# wisp-6-afe.net
KiCad netlist of a schematic drawn in Altium Designer
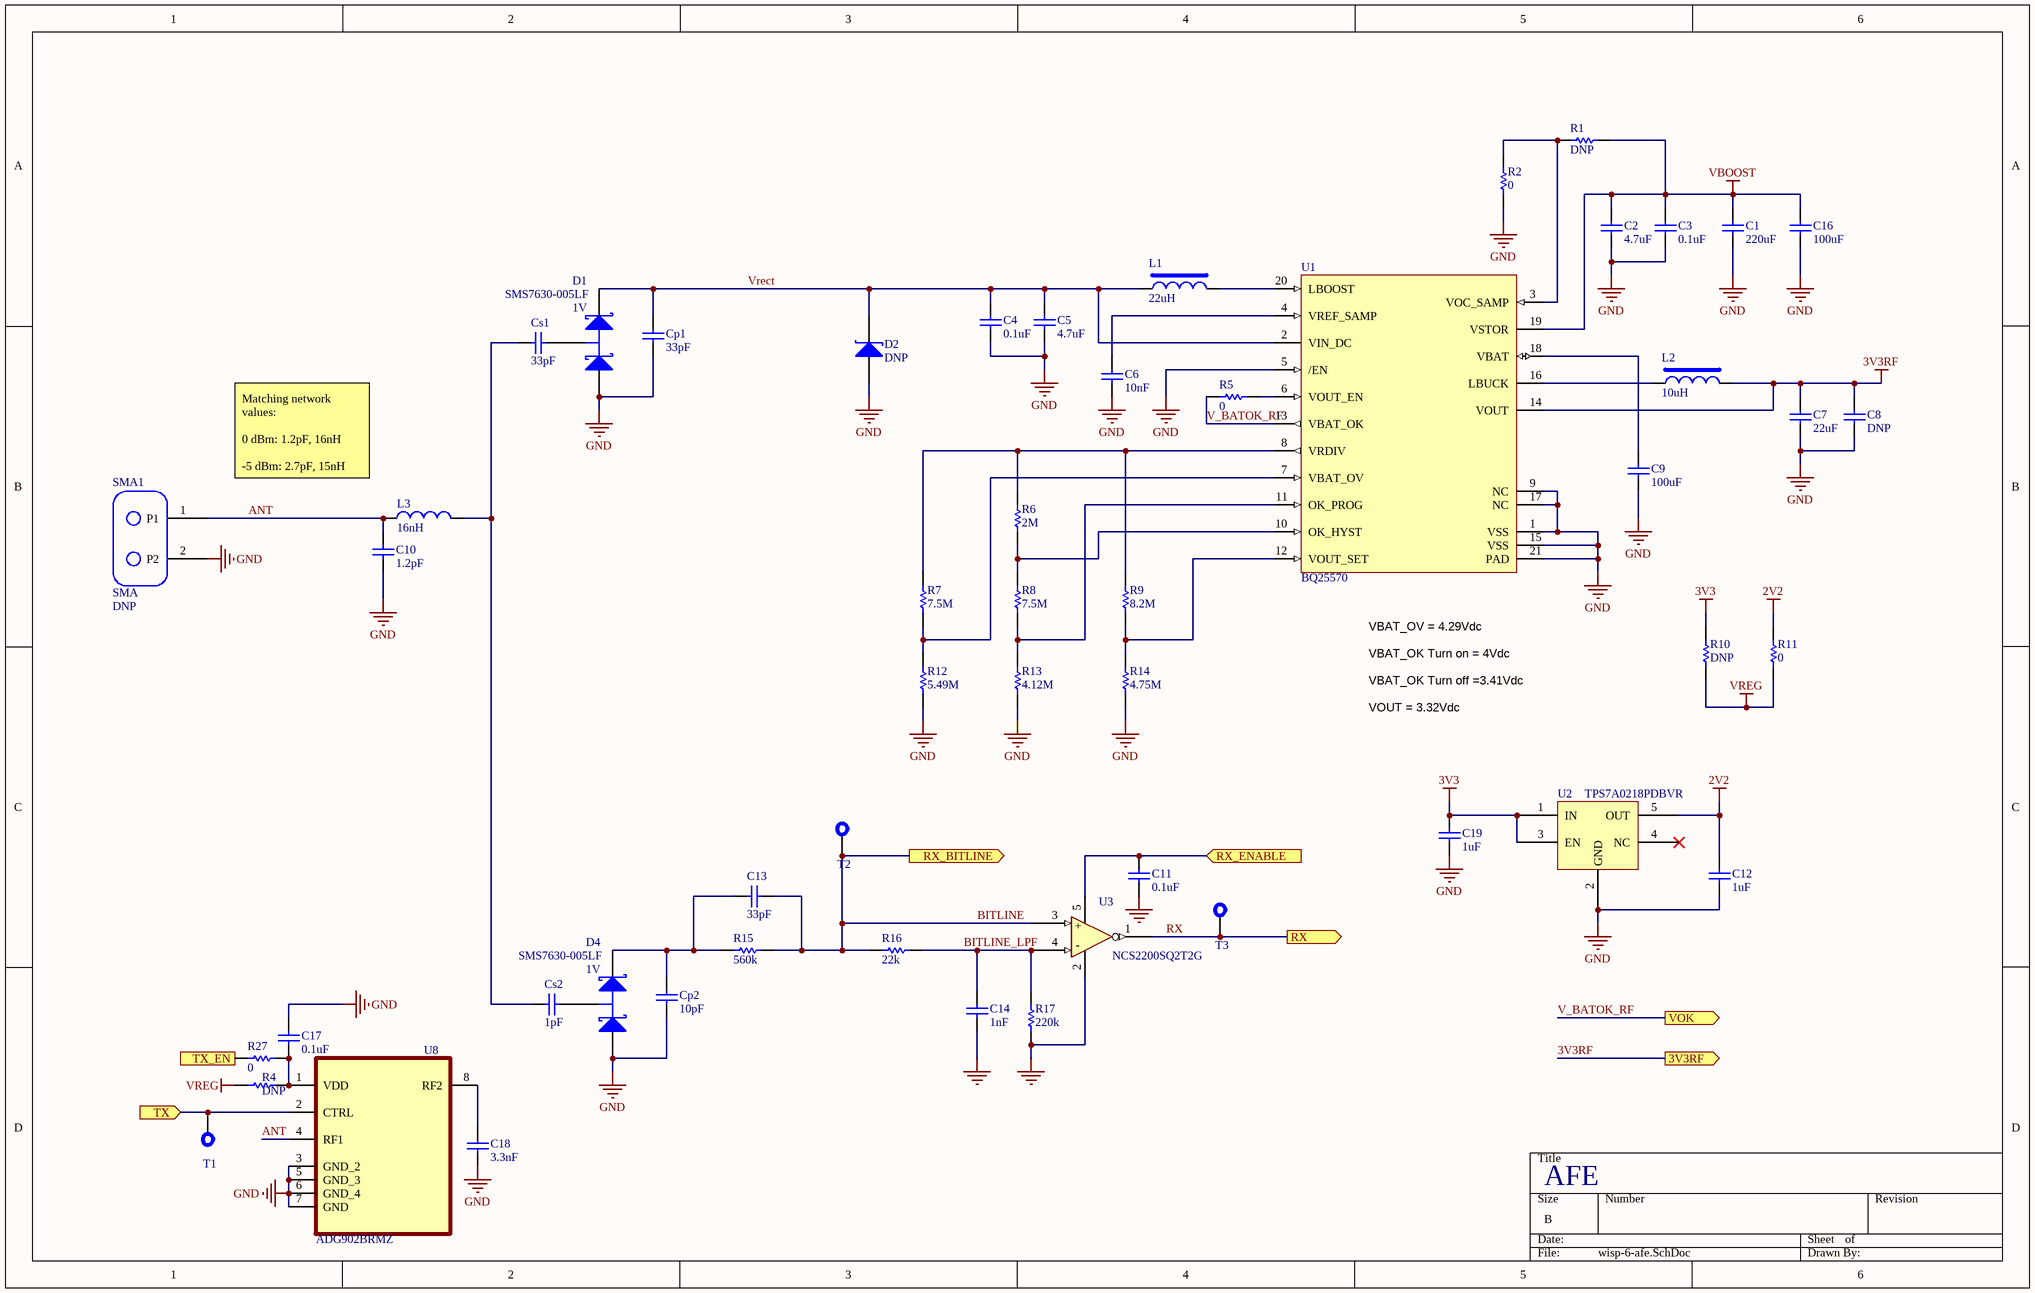
[diagram p0: wisp-6-afe.SchDoc]

(export (version "E")
  (design (tool "Eeschema 10.0.6"))
  (components
    (comp (ref "C1")
      (value "220uF")
      (footprint "1206")
      (description "CAP CER 220UF 6.3V X5R 1206")
      (fields
        (field (name "DIGI-KEY PART NUMBER") "490-13970-1-ND")
        (field (name "MANUFACTURER") "Murata Electronics")
      )
      (libsource (lib "WISP6") (part "C-220uF-6V3-X5R-1206"))
    )
    (comp (ref "C2")
      (value "4.7uF")
      (footprint "0402")
      (description "CAP CER 4.7UF 10V X5R 0402")
      (fields
        (field (name "DIGI-KEY PART NUMBER") "1276-1482-1-ND")
        (field (name "MANUFACTURER") "Samsung Electro-Mechanics")
      )
      (libsource (lib "WISP6") (part "C-4.7uF-10V-X5R-0402"))
    )
    (comp (ref "C3")
      (value "0.1uF")
      (footprint "0402")
      (description "CAP CER 100nF/0.1UF 10V X5R 0402")
      (fields
        (field (name "DIGI-KEY PART NUMBER") "1276-1022-1-ND")
        (field (name "MANUFACTURER") "Samsung Electro-Mechanics")
      )
      (libsource (lib "WISP6") (part "C-0.1uF-10V-X5R-0402"))
    )
    (comp (ref "C4")
      (value "0.1uF")
      (footprint "0402")
      (description "CAP CER 100nF/0.1UF 10V X5R 0402")
      (fields
        (field (name "DIGI-KEY PART NUMBER") "1276-1022-1-ND")
        (field (name "MANUFACTURER") "Samsung Electro-Mechanics")
      )
      (libsource (lib "WISP6") (part "C-0.1uF-10V-X5R-0402"))
    )
    (comp (ref "C5")
      (value "4.7uF")
      (footprint "0402")
      (description "CAP CER 4.7UF 10V X5R 0402")
      (fields
        (field (name "DIGI-KEY PART NUMBER") "1276-1482-1-ND")
        (field (name "MANUFACTURER") "Samsung Electro-Mechanics")
      )
      (libsource (lib "WISP6") (part "C-4.7uF-10V-X5R-0402"))
    )
    (comp (ref "C6")
      (value "10nF")
      (footprint "0402")
      (description "10000 pF ±10% 50V Ceramic Capacitor X7R 0402 (1005 Metric)")
      (fields
        (field (name "DIGI-KEY PART NUMBER") "1276-1028-1-ND")
        (field (name "MANUFACTURER") "Samsung Electro-Mechanics")
      )
      (libsource (lib "WISP6") (part "C-10nF-50V-X7R-0402"))
    )
    (comp (ref "C7")
      (value "22uF")
      (footprint "0402")
      (description "CAP CER 22UF 6.3V X5R 0402")
      (fields
        (field (name "DIGI-KEY PART NUMBER") "1276-7090-1-ND")
        (field (name "MANUFACTURER") "Samsung Electro-Mechanics")
      )
      (libsource (lib "WISP6") (part "C-22uF-6V3-X5R-0402"))
    )
    (comp (ref "C8")
      (value "DNP")
      (footprint "0402")
      (description "Ceramic Capacitor (Surface Mount)")
      (fields (field (name "Comment") "Generic capacitor"))
      (libsource (lib "WISP6") (part "cap"))
    )
    (comp (ref "C9")
      (value "100uF")
      (footprint "0805")
      (description "CAP CER 100UF 6.3V X5R 0805")
      (fields
        (field (name "DIGI-KEY PART NUMBER") "490-13981-1-ND")
        (field (name "MANUFACTURER") "Murata Electronics")
      )
      (libsource (lib "WISP6") (part "C-100uF-6V3-X5R-0805"))
    )
    (comp (ref "C10")
      (value "1.2pF")
      (footprint "0402")
      (description "Ceramic Capacitor (Surface Mount)")
      (fields
        (field (name "DIGI-KEY PART NUMBER") "712-QSCF500Q1R2A1GV001TCT-ND")
        (field (name "MANUFACTURER") "Johanson Technology Inc.")
      )
      (libsource (lib "WISP6") (part "cap"))
    )
    (comp (ref "C11")
      (value "0.1uF")
      (footprint "0402")
      (description "CAP CER 100nF/0.1UF 10V X5R 0402")
      (fields
        (field (name "DIGI-KEY PART NUMBER") "1276-1022-1-ND")
        (field (name "MANUFACTURER") "Samsung Electro-Mechanics")
      )
      (libsource (lib "WISP6") (part "C-0.1uF-10V-X5R-0402"))
    )
    (comp (ref "C12")
      (value "1uF")
      (footprint "0402")
      (description "CAP CER 1UF 10V X5R 0402")
      (fields
        (field (name "DIGI-KEY PART NUMBER") "1276-1076-1-ND")
        (field (name "MANUFACTURER") "Samsung Electro-Mechanics")
      )
      (libsource (lib "WISP6") (part "C-1uF-10V-X5R-0402"))
    )
    (comp (ref "C13")
      (value "33pF")
      (footprint "0402")
      (description "Ceramic Capacitor (Surface Mount)")
      (fields
        (field (name "DIGI-KEY PART NUMBER") "712-QSCF500Q330F1GV001TCT-ND")
        (field (name "MANUFACTURER") "Johanson Technology Inc.")
      )
      (libsource (lib "WISP6") (part "cap"))
    )
    (comp (ref "C14")
      (value "1nF")
      (footprint "0402")
      (description "CAP CER 1000PF 50V C0G/NP0 0402")
      (fields
        (field (name "DIGI-KEY PART NUMBER") "1276-1635-1-ND")
        (field (name "MANUFACTURER") "Samsung Electro-Mechanics")
      )
      (libsource (lib "WISP6") (part "C-1nF-50V-C0G-0402"))
    )
    (comp (ref "C16")
      (value "100uF")
      (footprint "0805")
      (description "CAP CER 100UF 6.3V X5R 0805")
      (fields
        (field (name "DIGI-KEY PART NUMBER") "490-13981-1-ND")
        (field (name "MANUFACTURER") "Murata Electronics")
      )
      (libsource (lib "WISP6") (part "C-100uF-6V3-X5R-0805"))
    )
    (comp (ref "C17")
      (value "0.1uF")
      (footprint "0402")
      (description "CAP CER 100nF/0.1UF 10V X5R 0402")
      (fields
        (field (name "DIGI-KEY PART NUMBER") "1276-1022-1-ND")
        (field (name "MANUFACTURER") "Samsung Electro-Mechanics")
      )
      (libsource (lib "WISP6") (part "C-0.1uF-10V-X5R-0402"))
    )
    (comp (ref "C18")
      (value "3.3nF")
      (footprint "0402")
      (description "Ceramic Capacitor (Surface Mount)")
      (fields
        (field (name "DIGI-KEY PART NUMBER") "490-GRM1555C1H332GE01DCT-ND")
        (field (name "MANUFACTURER") "Murata Electronics")
      )
      (libsource (lib "WISP6") (part "cap"))
    )
    (comp (ref "C19")
      (value "1uF")
      (footprint "0402")
      (description "CAP CER 1UF 10V X5R 0402")
      (fields
        (field (name "DIGI-KEY PART NUMBER") "1276-1076-1-ND")
        (field (name "MANUFACTURER") "Samsung Electro-Mechanics")
      )
      (libsource (lib "WISP6") (part "C-1uF-10V-X5R-0402"))
    )
    (comp (ref "Cp1")
      (value "33pF")
      (footprint "0402")
      (description "Ceramic Capacitor (Surface Mount)")
      (fields
        (field (name "DIGI-KEY PART NUMBER") "712-QSCF500Q330F1GV001TCT-ND")
        (field (name "MANUFACTURER") "Johanson Technology Inc.")
      )
      (libsource (lib "WISP6") (part "cap"))
    )
    (comp (ref "Cp2")
      (value "10pF")
      (footprint "0402")
      (description "Ceramic Capacitor (Surface Mount)")
      (fields
        (field (name "DIGI-KEY PART NUMBER") "712-QSCF500Q100F1GV001TCT-ND")
        (field (name "MANUFACTURER") "Johanson Technology Inc.")
      )
      (libsource (lib "WISP6") (part "cap"))
    )
    (comp (ref "Cs1")
      (value "33pF")
      (footprint "0402")
      (description "Ceramic Capacitor (Surface Mount)")
      (fields
        (field (name "DIGI-KEY PART NUMBER") "712-QSCF500Q330F1GV001TCT-ND")
        (field (name "MANUFACTURER") "Johanson Technology Inc.")
      )
      (libsource (lib "WISP6") (part "cap"))
    )
    (comp (ref "Cs2")
      (value "1pF")
      (footprint "0402")
      (description "Ceramic Capacitor (Surface Mount)")
      (fields
        (field (name "DIGI-KEY PART NUMBER") "712-QSCF500Q1R0B1GV001TCT-ND")
        (field (name "MANUFACTURER") "Johanson Technology Inc.")
      )
      (libsource (lib "WISP6") (part "cap"))
    )
    (comp (ref "D1")
      (value "SMS7630-005LF")
      (footprint "WISP_AD10:SOT23 - N")
      (description "RF diode schottky\r\nSOT-23 Series Pair\r\nLs=1.5nH")
      (fields
        (field (name "MANUFACTURER") "Skyworks Solutions Inc.")
        (field (name "DIGI-KEY PART NUMBER") "863-1699-1-ND")
        (field (name "ALTIUM_VALUE") "1V")
      )
      (libsource (lib "WISP6") (part "SMS7630-005LF"))
    )
    (comp (ref "D2")
      (value "DNP")
      (footprint "Zener_SOD-523")
      (description "Diode - Zener")
      (fields (field (name "Comment") "Generic diode - zener"))
      (libsource (lib "WISP6") (part "diode_zener"))
    )
    (comp (ref "D4")
      (value "SMS7630-005LF")
      (footprint "WISP_AD10:SOT23 - N")
      (description "RF diode schottky\r\nSOT-23 Series Pair\r\nLs=1.5nH")
      (fields
        (field (name "MANUFACTURER") "Skyworks Solutions Inc.")
        (field (name "DIGI-KEY PART NUMBER") "863-1699-1-ND")
        (field (name "ALTIUM_VALUE") "1V")
      )
      (libsource (lib "WISP6") (part "SMS7630-005LF"))
    )
    (comp (ref "L1")
      (value "22uH")
      (footprint "LPS4018")
      (description "22 µH Shielded Drum Core Inductor 650 mA 360mOhm Max Nonstandard")
      (fields
        (field (name "DIGI-KEY PART NUMBER") "2457-LPS4018-223MRC-ND")
        (field (name "MANUFACTURER") "Coilcraft")
      )
      (libsource (lib "WISP6") (part "Ind-22uH-650mA-20%-LPS4018"))
    )
    (comp (ref "L2")
      (value "10uH")
      (footprint "IND1008")
      (description "FIXED IND 10UH 800MA 625 MOHM")
      (fields
        (field (name "DIGI-KEY PART NUMBER") "732-74479889310CT-ND")
        (field (name "MANUFACTURER") "Würth Elektronik")
      )
      (libsource (lib "WISP6") (part "Ind-10uH-800mA-20%-1008"))
    )
    (comp (ref "L3")
      (value "16nH")
      (footprint "0603")
      (description "Inductor (Surface Mount)")
      (fields
        (field (name "DIGI-KEY PART NUMBER") "490-LQW18AS16NG00DCT-ND")
        (field (name "MANUFACTURER") "Murata Electronics")
      )
      (libsource (lib "WISP6") (part "ind"))
    )
    (comp (ref "R1")
      (value "DNP")
      (footprint "0402")
      (description "Chip Resistor (Surface Mount)")
      (fields (field (name "Comment") "Generic resistor"))
      (libsource (lib "WISP6") (part "res"))
    )
    (comp (ref "R2")
      (value "0")
      (footprint "0402")
      (description "RES 0 OHM JUMPER 1/16W 0402")
      (fields
        (field (name "MANUFACTURER") "YAGEO")
        (field (name "MANUFACTURER PART NUMBER") "RC0402JR-070RL")
      )
      (libsource (lib "WISP6") (part "R-0-0.063W-*-0402"))
    )
    (comp (ref "R4")
      (value "DNP")
      (footprint "0402")
      (description "Chip Resistor (Surface Mount)")
      (fields (field (name "Comment") "Generic resistor"))
      (libsource (lib "WISP6") (part "res"))
    )
    (comp (ref "R5")
      (value "0")
      (footprint "0402")
      (description "RES 0 OHM JUMPER 1/16W 0402")
      (fields
        (field (name "MANUFACTURER") "YAGEO")
        (field (name "MANUFACTURER PART NUMBER") "RC0402JR-070RL")
      )
      (libsource (lib "WISP6") (part "R-0-0.063W-*-0402"))
    )
    (comp (ref "R6")
      (value "2M")
      (footprint "0402")
      (description "RES 2M OHM 1% 1/16W 0402")
      (fields
        (field (name "MANUFACTURER") "YAGEO")
        (field (name "MANUFACTURER PART NUMBER") "RC0402FR-072ML")
      )
      (libsource (lib "WISP6") (part "R-2M-0.063W-1%-0402"))
    )
    (comp (ref "R7")
      (value "7.5M")
      (footprint "0402")
      (description "RES 7.5M OHM 5% 1/16W 0402")
      (fields
        (field (name "MANUFACTURER") "YAGEO")
        (field (name "MANUFACTURER PART NUMBER") "RC0402JR-077M5L")
      )
      (libsource (lib "WISP6") (part "R-7M5-0.063W-5%-0402"))
    )
    (comp (ref "R8")
      (value "7.5M")
      (footprint "0402")
      (description "RES 7.5M OHM 5% 1/16W 0402")
      (fields
        (field (name "MANUFACTURER") "YAGEO")
        (field (name "MANUFACTURER PART NUMBER") "RC0402JR-077M5L")
      )
      (libsource (lib "WISP6") (part "R-7M5-0.063W-5%-0402"))
    )
    (comp (ref "R9")
      (value "8.2M")
      (footprint "0402")
      (description "8.2 MOhms ±1% 0.063W, 1/16W Chip Resistor 0402 (1005 Metric) Moisture Resistant Thick Film")
      (fields
        (field (name "MANUFACTURER") "YAGEO")
        (field (name "MANUFACTURER PART NUMBER") "RC0402FR-078M2L")
      )
      (libsource (lib "WISP6") (part "R-8M2-0.063W-1%-0402"))
    )
    (comp (ref "R10")
      (value "DNP")
      (footprint "0402")
      (description "Chip Resistor (Surface Mount)")
      (fields (field (name "Comment") "Generic resistor"))
      (libsource (lib "WISP6") (part "res"))
    )
    (comp (ref "R11")
      (value "0")
      (footprint "0402")
      (description "RES 0 OHM JUMPER 1/16W 0402")
      (fields
        (field (name "MANUFACTURER") "YAGEO")
        (field (name "MANUFACTURER PART NUMBER") "RC0402JR-070RL")
      )
      (libsource (lib "WISP6") (part "R-0-0.063W-*-0402"))
    )
    (comp (ref "R12")
      (value "5.49M")
      (footprint "0402")
      (description "5.49 MOhms ±1% 0.063W, 1/16W Chip Resistor 0402 (1005 Metric) Moisture Resistant Thick Film")
      (fields
        (field (name "MANUFACTURER") "YAGEO")
        (field (name "MANUFACTURER PART NUMBER") "RC0402FR-075M49L")
      )
      (libsource (lib "WISP6") (part "R-5M49-0.063W-1%-0402"))
    )
    (comp (ref "R13")
      (value "4.12M")
      (footprint "0402")
      (description "RES 4.12M OHM 1% 1/16W 0402")
      (fields
        (field (name "MANUFACTURER") "YAGEO")
        (field (name "MANUFACTURER PART NUMBER") "RC0402FR-074M12L")
      )
      (libsource (lib "WISP6") (part "R-4M12-0.063W-1%-0402"))
    )
    (comp (ref "R14")
      (value "4.75M")
      (footprint "0402")
      (description "RES 4.75M OHM 1% 1/16W 0402")
      (fields
        (field (name "MANUFACTURER") "YAGEO")
        (field (name "MANUFACTURER PART NUMBER") "RC0402FR-074M75L")
      )
      (libsource (lib "WISP6") (part "R-4M75-0.063W-1%-0402"))
    )
    (comp (ref "R15")
      (value "560k")
      (footprint "0402")
      (description "RES 560K OHM 1% 1/16W 0402")
      (fields
        (field (name "MANUFACTURER") "YAGEO")
        (field (name "MANUFACTURER PART NUMBER") "RC0402FR-07560KL")
      )
      (libsource (lib "WISP6") (part "R-560k-0.063W-1%-0402"))
    )
    (comp (ref "R16")
      (value "22k")
      (footprint "0402")
      (description "RES 22K OHM 1% 1/16W 0402")
      (fields
        (field (name "MANUFACTURER") "YAGEO")
        (field (name "MANUFACTURER PART NUMBER") "RC0402FR-0722KL")
      )
      (libsource (lib "WISP6") (part "R-22k-0.063W-1%-0402"))
    )
    (comp (ref "R17")
      (value "220k")
      (footprint "0402")
      (description "RES 220K OHM 1% 1/16W 0402")
      (fields
        (field (name "MANUFACTURER") "YAGEO")
        (field (name "MANUFACTURER PART NUMBER") "RC0402FR-07220KL")
      )
      (libsource (lib "WISP6") (part "R-220k-0.063W-1%-0402"))
    )
    (comp (ref "R27")
      (value "0")
      (footprint "0402")
      (description "RES 0 OHM JUMPER 1/16W 0402")
      (fields
        (field (name "MANUFACTURER") "YAGEO")
        (field (name "MANUFACTURER PART NUMBER") "RC0402JR-070RL")
      )
      (libsource (lib "WISP6") (part "R-0-0.063W-*-0402"))
    )
    (comp (ref "SMA1")
      (value "SMA")
      (footprint "SMA - Hole - 2 Pin")
      (description "Two pin SMA connector wisp")
      (fields (field (name "ALTIUM_VALUE") "DNP"))
      (libsource (lib "WISP6") (part "SMA - Hole - 2 Pin"))
    )
    (comp (ref "T1")
      (value "TP")
      (footprint "Test Point - Via")
      (description "Test Point, via no BOM")
      (libsource (lib "WISP6") (part "Test Point Via"))
    )
    (comp (ref "T2")
      (value "TP")
      (footprint "Test Point - Via")
      (description "Test Point, via no BOM")
      (libsource (lib "WISP6") (part "Test Point Via"))
    )
    (comp (ref "T3")
      (value "TP")
      (footprint "Test Point - Via")
      (description "Test Point, via no BOM")
      (libsource (lib "WISP6") (part "Test Point Via"))
    )
    (comp (ref "U1")
      (value "BQ25570")
      (footprint "BQ25570")
      (description "Buck-boost charger Energy Harvesting PMIC 20-VQFN (3.5x3.5)")
      (fields
        (field (name "DIGI-KEY PART NUMBER") "296-37014-1-ND")
        (field (name "MANUFACTURER") "Texas Instruments")
      )
      (libsource (lib "WISP6") (part "BQ25570"))
    )
    (comp (ref "U2")
      (value "TPS7A0218PDBVR")
      (footprint "SOT23-5")
      (description "Linear Voltage Regulator IC Positive Fixed 1 Output 200mA SOT-23-5")
      (fields
        (field (name "MANUFACTURER") "Texas Instruments")
        (field (name "DIGI-KEY PART NUMBER") "296-TPS7A0218PDBVRCT-ND")
      )
      (libsource (lib "WISP6") (part "TPS7A0218PDBVR"))
    )
    (comp (ref "U3")
      (value "NCS2200SQ2T2G")
      (footprint "SC70-5")
      (description "Comparator Standard (General Purpose) Complementary, Rail-to-Rail SC-88A (SC-70-5/SOT-353)")
      (fields
        (field (name "DIGI-KEY PART NUMBER") "NCS2200SQ2T2GOSCT-ND")
        (field (name "MANUFACTURER") "onsemi")
      )
      (libsource (lib "WISP6") (part "NCS2200"))
    )
    (comp (ref "U8")
      (value "ADG902BRMZ")
      (footprint "SOP65P490X110-8N:SOP65P490X110-8N")
      (description "RF Switch IC General Purpose SPST 2.5GHz 50Ohm 8-MSOP")
      (fields
        (field (name "MANUFACTURER") "Analog Devices")
        (field (name "DIGI-KEY PART NUMBER") "ADG902BRMZ-ND")
      )
      (libsource (lib "WISP6") (part "ADG902BRMZ"))
    )
  )
  (nets
    (net (code "1") (name "/ANT") (class "Default")
      (node (ref "C10") (pin "2") (pinfunction "2_2") (pintype "passive"))
      (node (ref "L3") (pin "1") (pinfunction "1_1") (pintype "passive"))
      (node (ref "SMA1") (pin "1") (pinfunction "P1_1") (pintype "passive"))
      (node (ref "U8") (pin "4") (pinfunction "RF1_4") (pintype "passive"))
    )
    (net (code "2") (name "/BITLINE") (class "Default")
      (node (ref "C13") (pin "1") (pinfunction "1_1") (pintype "passive"))
      (node (ref "R15") (pin "2") (pinfunction "2_2") (pintype "passive"))
      (node (ref "R16") (pin "1") (pinfunction "1_1") (pintype "passive"))
      (node (ref "T2") (pin "0") (pinfunction "0_0") (pintype "passive"))
      (node (ref "U3") (pin "3") (pinfunction "IN+_3") (pintype "input"))
    )
    (net (code "3") (name "/BITLINE_LPF") (class "Default")
      (node (ref "C14") (pin "2") (pinfunction "2_2") (pintype "passive"))
      (node (ref "R16") (pin "2") (pinfunction "2_2") (pintype "passive"))
      (node (ref "R17") (pin "2") (pinfunction "2_2") (pintype "passive"))
      (node (ref "U3") (pin "4") (pinfunction "In-_4") (pintype "input"))
    )
    (net (code "4") (name "/RX") (class "Default")
      (node (ref "T3") (pin "0") (pinfunction "0_0") (pintype "passive"))
      (node (ref "U3") (pin "1") (pinfunction "OUT_1") (pintype "output"))
    )
    (net (code "5") (name "/RX_ENABLE") (class "Default")
      (node (ref "C11") (pin "2") (pinfunction "2_2") (pintype "passive"))
      (node (ref "U3") (pin "5") (pinfunction "VDD_5") (pintype "power_in"))
    )
    (net (code "6") (name "/TX") (class "Default")
      (node (ref "T1") (pin "0") (pinfunction "0_0") (pintype "passive"))
      (node (ref "U8") (pin "2") (pinfunction "CTRL_2") (pintype "passive"))
    )
    (net (code "7") (name "/TX_EN") (class "Default")
      (node (ref "R27") (pin "2") (pinfunction "2_2") (pintype "passive"))
    )
    (net (code "8") (name "/V_BATOK_RF") (class "Default")
      (node (ref "R5") (pin "1") (pinfunction "1_1") (pintype "passive"))
      (node (ref "U1") (pin "13") (pinfunction "VBAT_OK_13") (pintype "output"))
    )
    (net (code "9") (name "/Vrect") (class "Default")
      (node (ref "C4") (pin "2") (pinfunction "2_2") (pintype "passive"))
      (node (ref "C5") (pin "2") (pinfunction "2_2") (pintype "passive"))
      (node (ref "Cp1") (pin "1") (pinfunction "1_1") (pintype "passive"))
      (node (ref "D1") (pin "2") (pinfunction "K_2") (pintype "passive"))
      (node (ref "D2") (pin "2") (pinfunction "K_2") (pintype "passive"))
      (node (ref "L1") (pin "1") (pinfunction "1_1") (pintype "passive"))
      (node (ref "U1") (pin "2") (pinfunction "VIN_DC_2") (pintype "passive"))
    )
    (net (code "10") (name "2V2") (class "Default")
      (node (ref "C12") (pin "2") (pinfunction "2_2") (pintype "passive"))
      (node (ref "R11") (pin "2") (pinfunction "2_2") (pintype "passive"))
      (node (ref "U2") (pin "5") (pinfunction "OUT_5") (pintype "passive"))
    )
    (net (code "11") (name "3V3") (class "Default")
      (node (ref "C19") (pin "2") (pinfunction "2_2") (pintype "passive"))
      (node (ref "R10") (pin "2") (pinfunction "2_2") (pintype "passive"))
      (node (ref "U2") (pin "1") (pinfunction "IN_1") (pintype "passive"))
      (node (ref "U2") (pin "3") (pinfunction "EN_3") (pintype "passive"))
    )
    (net (code "12") (name "3V3RF") (class "Default")
      (node (ref "C7") (pin "2") (pinfunction "2_2") (pintype "passive"))
      (node (ref "C8") (pin "2") (pinfunction "2_2") (pintype "passive"))
      (node (ref "L2") (pin "2") (pinfunction "2_2") (pintype "passive"))
      (node (ref "U1") (pin "14") (pinfunction "VOUT_14") (pintype "passive"))
    )
    (net (code "13") (name "GND") (class "Default")
      (node (ref "C1") (pin "1") (pinfunction "1_1") (pintype "passive"))
      (node (ref "C10") (pin "1") (pinfunction "1_1") (pintype "passive"))
      (node (ref "C11") (pin "1") (pinfunction "1_1") (pintype "passive"))
      (node (ref "C12") (pin "1") (pinfunction "1_1") (pintype "passive"))
      (node (ref "C14") (pin "1") (pinfunction "1_1") (pintype "passive"))
      (node (ref "C16") (pin "1") (pinfunction "1_1") (pintype "passive"))
      (node (ref "C17") (pin "2") (pinfunction "2_2") (pintype "passive"))
      (node (ref "C18") (pin "1") (pinfunction "1_1") (pintype "passive"))
      (node (ref "C19") (pin "1") (pinfunction "1_1") (pintype "passive"))
      (node (ref "C2") (pin "1") (pinfunction "1_1") (pintype "passive"))
      (node (ref "C3") (pin "1") (pinfunction "1_1") (pintype "passive"))
      (node (ref "C4") (pin "1") (pinfunction "1_1") (pintype "passive"))
      (node (ref "C5") (pin "1") (pinfunction "1_1") (pintype "passive"))
      (node (ref "C6") (pin "1") (pinfunction "1_1") (pintype "passive"))
      (node (ref "C7") (pin "1") (pinfunction "1_1") (pintype "passive"))
      (node (ref "C8") (pin "1") (pinfunction "1_1") (pintype "passive"))
      (node (ref "C9") (pin "1") (pinfunction "1_1") (pintype "passive"))
      (node (ref "Cp1") (pin "2") (pinfunction "2_2") (pintype "passive"))
      (node (ref "Cp2") (pin "2") (pinfunction "2_2") (pintype "passive"))
      (node (ref "D1") (pin "1") (pinfunction "A_1") (pintype "passive"))
      (node (ref "D2") (pin "1") (pinfunction "A_1") (pintype "passive"))
      (node (ref "D4") (pin "1") (pinfunction "A_1") (pintype "passive"))
      (node (ref "R12") (pin "1") (pinfunction "1_1") (pintype "passive"))
      (node (ref "R13") (pin "1") (pinfunction "1_1") (pintype "passive"))
      (node (ref "R14") (pin "1") (pinfunction "1_1") (pintype "passive"))
      (node (ref "R17") (pin "1") (pinfunction "1_1") (pintype "passive"))
      (node (ref "R2") (pin "1") (pinfunction "1_1") (pintype "passive"))
      (node (ref "SMA1") (pin "2") (pinfunction "P2_2") (pintype "passive"))
      (node (ref "U1") (pin "1") (pinfunction "VSS_1") (pintype "passive"))
      (node (ref "U1") (pin "15") (pinfunction "VSS_15") (pintype "passive"))
      (node (ref "U1") (pin "17") (pinfunction "NC_17") (pintype "passive"))
      (node (ref "U1") (pin "21") (pinfunction "PAD_21") (pintype "passive"))
      (node (ref "U1") (pin "5") (pinfunction "/EN_5") (pintype "input"))
      (node (ref "U1") (pin "9") (pinfunction "NC_9") (pintype "passive"))
      (node (ref "U2") (pin "2") (pinfunction "GND_2") (pintype "passive"))
      (node (ref "U3") (pin "2") (pinfunction "Gnd_2") (pintype "power_in"))
      (node (ref "U8") (pin "3") (pinfunction "GND_2_3") (pintype "passive"))
      (node (ref "U8") (pin "5") (pinfunction "GND_3_5") (pintype "passive"))
      (node (ref "U8") (pin "6") (pinfunction "GND_4_6") (pintype "passive"))
      (node (ref "U8") (pin "7") (pinfunction "GND_7") (pintype "passive"))
    )
    (net (code "14") (name "Net-(Cs1-Pad2)") (class "Default")
      (node (ref "Cs1") (pin "2") (pinfunction "2_2") (pintype "passive"))
      (node (ref "Cs2") (pin "2") (pinfunction "2_2") (pintype "passive"))
      (node (ref "L3") (pin "2") (pinfunction "2_2") (pintype "passive"))
    )
    (net (code "15") (name "Net-(D1-C)") (class "Default")
      (node (ref "Cs1") (pin "1") (pinfunction "1_1") (pintype "passive"))
      (node (ref "D1") (pin "3") (pinfunction "C_3") (pintype "passive"))
    )
    (net (code "16") (name "Net-(D4-C)") (class "Default")
      (node (ref "Cs2") (pin "1") (pinfunction "1_1") (pintype "passive"))
      (node (ref "D4") (pin "3") (pinfunction "C_3") (pintype "passive"))
    )
    (net (code "17") (name "Net-(D4-K)") (class "Default")
      (node (ref "C13") (pin "2") (pinfunction "2_2") (pintype "passive"))
      (node (ref "Cp2") (pin "1") (pinfunction "1_1") (pintype "passive"))
      (node (ref "D4") (pin "2") (pinfunction "K_2") (pintype "passive"))
      (node (ref "R15") (pin "1") (pinfunction "1_1") (pintype "passive"))
    )
    (net (code "18") (name "Net-(U1-LBOOST)") (class "Default")
      (node (ref "L1") (pin "2") (pinfunction "2_2") (pintype "passive"))
      (node (ref "U1") (pin "20") (pinfunction "LBOOST_20") (pintype "input"))
    )
    (net (code "19") (name "Net-(U1-LBUCK)") (class "Default")
      (node (ref "L2") (pin "1") (pinfunction "1_1") (pintype "passive"))
      (node (ref "U1") (pin "16") (pinfunction "LBUCK_16") (pintype "passive"))
    )
    (net (code "20") (name "Net-(U1-OK_HYST)") (class "Default")
      (node (ref "R6") (pin "1") (pinfunction "1_1") (pintype "passive"))
      (node (ref "R8") (pin "2") (pinfunction "2_2") (pintype "passive"))
      (node (ref "U1") (pin "10") (pinfunction "OK_HYST_10") (pintype "input"))
    )
    (net (code "21") (name "Net-(U1-OK_PROG)") (class "Default")
      (node (ref "R13") (pin "2") (pinfunction "2_2") (pintype "passive"))
      (node (ref "R8") (pin "1") (pinfunction "1_1") (pintype "passive"))
      (node (ref "U1") (pin "11") (pinfunction "OK_PROG_11") (pintype "input"))
    )
    (net (code "22") (name "Net-(U1-VBAT)") (class "Default")
      (node (ref "C9") (pin "2") (pinfunction "2_2") (pintype "passive"))
      (node (ref "U1") (pin "18") (pinfunction "VBAT_18") (pintype "bidirectional"))
    )
    (net (code "23") (name "Net-(U1-VBAT_OV)") (class "Default")
      (node (ref "R12") (pin "2") (pinfunction "2_2") (pintype "passive"))
      (node (ref "R7") (pin "1") (pinfunction "1_1") (pintype "passive"))
      (node (ref "U1") (pin "7") (pinfunction "VBAT_OV_7") (pintype "input"))
    )
    (net (code "24") (name "Net-(U1-VOC_SAMP)") (class "Default")
      (node (ref "R1") (pin "1") (pinfunction "1_1") (pintype "passive"))
      (node (ref "R2") (pin "2") (pinfunction "2_2") (pintype "passive"))
      (node (ref "U1") (pin "3") (pinfunction "VOC_SAMP_3") (pintype "input"))
    )
    (net (code "25") (name "Net-(U1-VOUT_EN)") (class "Default")
      (node (ref "R5") (pin "2") (pinfunction "2_2") (pintype "passive"))
      (node (ref "U1") (pin "6") (pinfunction "VOUT_EN_6") (pintype "input"))
    )
    (net (code "26") (name "Net-(U1-VOUT_SET)") (class "Default")
      (node (ref "R14") (pin "2") (pinfunction "2_2") (pintype "passive"))
      (node (ref "R9") (pin "1") (pinfunction "1_1") (pintype "passive"))
      (node (ref "U1") (pin "12") (pinfunction "VOUT_SET_12") (pintype "input"))
    )
    (net (code "27") (name "Net-(U1-VRDIV)") (class "Default")
      (node (ref "R6") (pin "2") (pinfunction "2_2") (pintype "passive"))
      (node (ref "R7") (pin "2") (pinfunction "2_2") (pintype "passive"))
      (node (ref "R9") (pin "2") (pinfunction "2_2") (pintype "passive"))
      (node (ref "U1") (pin "8") (pinfunction "VRDIV_8") (pintype "output"))
    )
    (net (code "28") (name "Net-(U1-VREF_SAMP)") (class "Default")
      (node (ref "C6") (pin "2") (pinfunction "2_2") (pintype "passive"))
      (node (ref "U1") (pin "4") (pinfunction "VREF_SAMP_4") (pintype "input"))
    )
    (net (code "29") (name "Net-(U8-RF2)") (class "Default")
      (node (ref "C18") (pin "2") (pinfunction "2_2") (pintype "passive"))
      (node (ref "U8") (pin "8") (pinfunction "RF2_8") (pintype "passive"))
    )
    (net (code "30") (name "Net-(U8-VDD)") (class "Default")
      (node (ref "C17") (pin "1") (pinfunction "1_1") (pintype "passive"))
      (node (ref "R27") (pin "1") (pinfunction "1_1") (pintype "passive"))
      (node (ref "R4") (pin "1") (pinfunction "1_1") (pintype "passive"))
      (node (ref "U8") (pin "1") (pinfunction "VDD_1") (pintype "power_in"))
    )
    (net (code "31") (name "VBOOST") (class "Default")
      (node (ref "C1") (pin "2") (pinfunction "2_2") (pintype "passive"))
      (node (ref "C16") (pin "2") (pinfunction "2_2") (pintype "passive"))
      (node (ref "C2") (pin "2") (pinfunction "2_2") (pintype "passive"))
      (node (ref "C3") (pin "2") (pinfunction "2_2") (pintype "passive"))
      (node (ref "R1") (pin "2") (pinfunction "2_2") (pintype "passive"))
      (node (ref "U1") (pin "19") (pinfunction "VSTOR_19") (pintype "passive"))
    )
    (net (code "32") (name "VREG") (class "Default")
      (node (ref "R10") (pin "1") (pinfunction "1_1") (pintype "passive"))
      (node (ref "R11") (pin "1") (pinfunction "1_1") (pintype "passive"))
      (node (ref "R4") (pin "2") (pinfunction "2_2") (pintype "passive"))
    )
    (net (code "33") (name "unconnected-(U2-NC-Pad4)") (class "Default")
      (node (ref "U2") (pin "4") (pinfunction "NC_4") (pintype "passive+no_connect"))
    )
  )
)
